# Keg_Cop_-_Devel.net
KiCad netlist of a schematic drawn in EAGLE
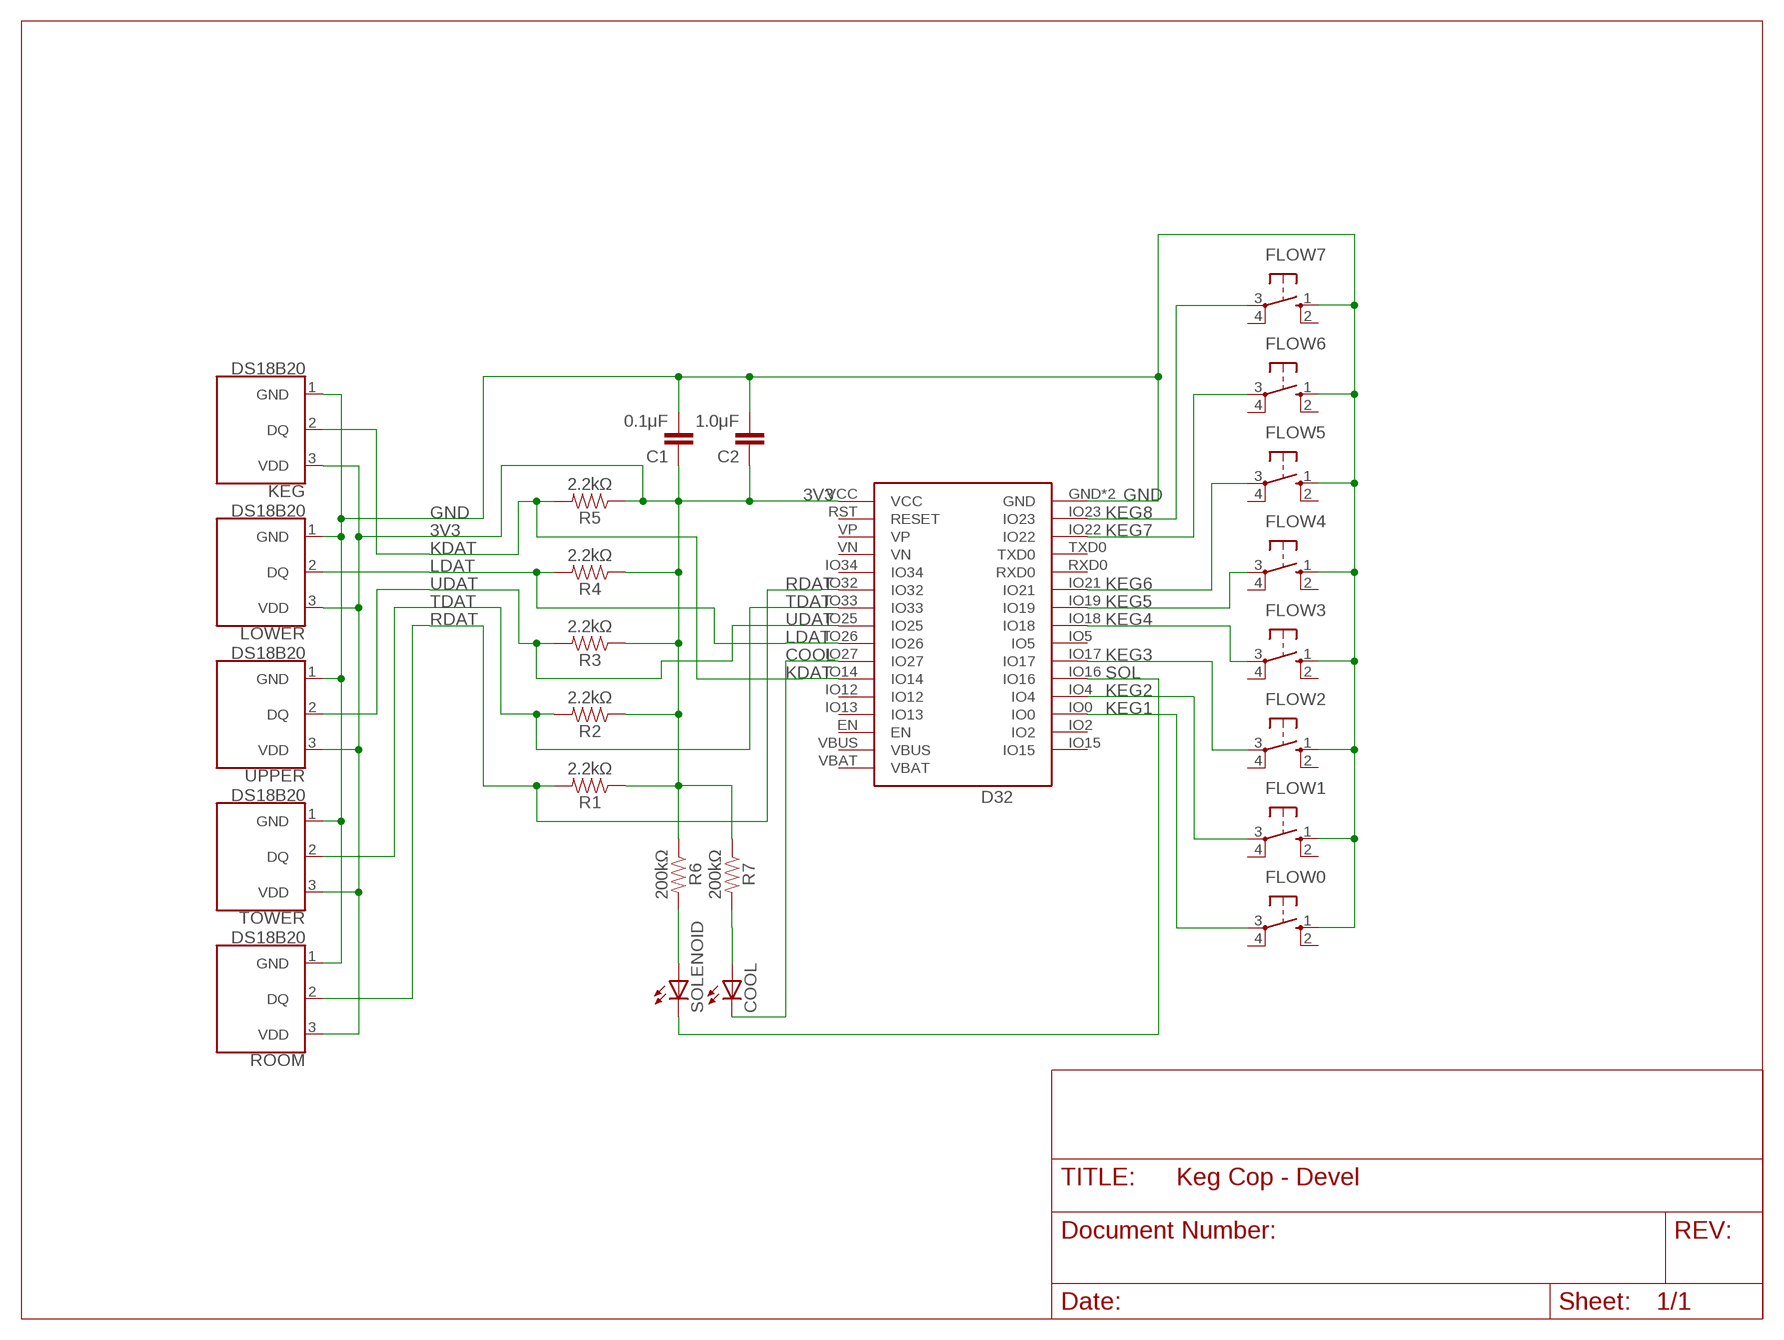
[diagram p0: schematic, sheet 1]

(export (version "E")
  (design (tool "Eeschema 10.0.6"))
  (components
    (comp (ref "C1")
      (value "0.1μF")
      (footprint "eagle-import:CAP_PTH-2.54")
      (libsource (lib "eagle-import") (part "CAP_CERAMIC_2.54"))
    )
    (comp (ref "C2")
      (value "1.0μF")
      (footprint "eagle-import:CAP_PTH-2.54")
      (libsource (lib "eagle-import") (part "CAP_CERAMIC_2.54"))
    )
    (comp (ref "COOL")
      (value "LED3MM")
      (footprint "eagle-import:LED3MM")
      (libsource (lib "eagle-import") (part "LED3MM"))
    )
    (comp (ref "D32")
      (value "Lolin D32")
      (footprint "eagle-import:D32_NO_BATT")
      (libsource (lib "eagle-import") (part "WEMOS-D32D32_NO_BATT"))
    )
    (comp (ref "FLOW0")
      (value "10-XX")
      (footprint "eagle-import:B3F-10XX")
      (fields (field (name "MPN") "B3F-1000"))
      (libsource (lib "eagle-import") (part "10-XX"))
    )
    (comp (ref "FLOW1")
      (value "10-XX")
      (footprint "eagle-import:B3F-10XX")
      (fields (field (name "MPN") "B3F-1000"))
      (libsource (lib "eagle-import") (part "10-XX"))
    )
    (comp (ref "FLOW2")
      (value "10-XX")
      (footprint "eagle-import:B3F-10XX")
      (fields (field (name "MPN") "B3F-1000"))
      (libsource (lib "eagle-import") (part "10-XX"))
    )
    (comp (ref "FLOW3")
      (value "10-XX")
      (footprint "eagle-import:B3F-10XX")
      (fields (field (name "MPN") "B3F-1000"))
      (libsource (lib "eagle-import") (part "10-XX"))
    )
    (comp (ref "FLOW4")
      (value "10-XX")
      (footprint "eagle-import:B3F-10XX")
      (fields (field (name "MPN") "B3F-1000"))
      (libsource (lib "eagle-import") (part "10-XX"))
    )
    (comp (ref "FLOW5")
      (value "10-XX")
      (footprint "eagle-import:B3F-10XX")
      (fields (field (name "MPN") "B3F-1000"))
      (libsource (lib "eagle-import") (part "10-XX"))
    )
    (comp (ref "FLOW6")
      (value "10-XX")
      (footprint "eagle-import:B3F-10XX")
      (fields (field (name "MPN") "B3F-1000"))
      (libsource (lib "eagle-import") (part "10-XX"))
    )
    (comp (ref "FLOW7")
      (value "10-XX")
      (footprint "eagle-import:B3F-10XX")
      (fields (field (name "MPN") "B3F-1000"))
      (libsource (lib "eagle-import") (part "10-XX"))
    )
    (comp (ref "KEG")
      (value "DS18B20")
      (footprint "eagle-import:TO-92-AMMO")
      (libsource (lib "eagle-import") (part "DS18B20"))
    )
    (comp (ref "LOWER")
      (value "DS18B20")
      (footprint "eagle-import:TO-92-AMMO")
      (libsource (lib "eagle-import") (part "DS18B20"))
    )
    (comp (ref "R1")
      (value "2.2kΩ")
      (footprint "eagle-import:AXIAL-0.3")
      (libsource (lib "eagle-import") (part "RESISTORAXIAL-0.3"))
    )
    (comp (ref "R2")
      (value "2.2kΩ")
      (footprint "eagle-import:AXIAL-0.3")
      (libsource (lib "eagle-import") (part "RESISTORAXIAL-0.3"))
    )
    (comp (ref "R3")
      (value "2.2kΩ")
      (footprint "eagle-import:AXIAL-0.3")
      (libsource (lib "eagle-import") (part "RESISTORAXIAL-0.3"))
    )
    (comp (ref "R4")
      (value "2.2kΩ")
      (footprint "eagle-import:AXIAL-0.3")
      (libsource (lib "eagle-import") (part "RESISTORAXIAL-0.3"))
    )
    (comp (ref "R5")
      (value "2.2kΩ")
      (footprint "eagle-import:AXIAL-0.3")
      (libsource (lib "eagle-import") (part "RESISTORAXIAL-0.3"))
    )
    (comp (ref "R6")
      (value "200kΩ")
      (footprint "eagle-import:AXIAL-0.3")
      (libsource (lib "eagle-import") (part "RESISTORAXIAL-0.3"))
    )
    (comp (ref "R7")
      (value "200kΩ")
      (footprint "eagle-import:AXIAL-0.3")
      (libsource (lib "eagle-import") (part "RESISTORAXIAL-0.3"))
    )
    (comp (ref "ROOM")
      (value "DS18B20")
      (footprint "eagle-import:TO-92-AMMO")
      (libsource (lib "eagle-import") (part "DS18B20"))
    )
    (comp (ref "SOLENOID")
      (value "LED3MM")
      (footprint "eagle-import:LED3MM")
      (libsource (lib "eagle-import") (part "LED3MM"))
    )
    (comp (ref "TOWER")
      (value "DS18B20")
      (footprint "eagle-import:TO-92-AMMO")
      (libsource (lib "eagle-import") (part "DS18B20"))
    )
    (comp (ref "UPPER")
      (value "DS18B20")
      (footprint "eagle-import:TO-92-AMMO")
      (libsource (lib "eagle-import") (part "DS18B20"))
    )
  )
  (nets
    (net (code "1") (name "/3V3") (class "Default")
      (node (ref "C1") (pin "1") (pinfunction "1_1") (pintype "passive"))
      (node (ref "C2") (pin "1") (pinfunction "1_1") (pintype "passive"))
      (node (ref "D32") (pin "VCC") (pinfunction "VCC_VCC") (pintype "power_in"))
      (node (ref "KEG") (pin "3") (pinfunction "VDD_3") (pintype "power_in"))
      (node (ref "LOWER") (pin "3") (pinfunction "VDD_3") (pintype "power_in"))
      (node (ref "R1") (pin "P$1") (pinfunction "1_P$1") (pintype "passive"))
      (node (ref "R2") (pin "P$1") (pinfunction "1_P$1") (pintype "passive"))
      (node (ref "R3") (pin "P$1") (pinfunction "1_P$1") (pintype "passive"))
      (node (ref "R4") (pin "P$1") (pinfunction "1_P$1") (pintype "passive"))
      (node (ref "R5") (pin "P$1") (pinfunction "1_P$1") (pintype "passive"))
      (node (ref "R6") (pin "P$1") (pinfunction "1_P$1") (pintype "passive"))
      (node (ref "R7") (pin "P$1") (pinfunction "1_P$1") (pintype "passive"))
      (node (ref "ROOM") (pin "3") (pinfunction "VDD_3") (pintype "power_in"))
      (node (ref "TOWER") (pin "3") (pinfunction "VDD_3") (pintype "power_in"))
      (node (ref "UPPER") (pin "3") (pinfunction "VDD_3") (pintype "power_in"))
    )
    (net (code "2") (name "/COOL") (class "Default")
      (node (ref "COOL") (pin "K") (pinfunction "C_K") (pintype "passive"))
      (node (ref "D32") (pin "IO27") (pinfunction "IO27_IO27") (pintype "bidirectional"))
    )
    (net (code "3") (name "/GND") (class "Default")
      (node (ref "C1") (pin "2") (pinfunction "2_2") (pintype "passive"))
      (node (ref "C2") (pin "2") (pinfunction "2_2") (pintype "passive"))
      (node (ref "D32") (pin "GND") (pinfunction "GND_GND") (pintype "power_in"))
      (node (ref "D32") (pin "GND2") (pinfunction "GND_GND2") (pintype "power_in"))
      (node (ref "FLOW0") (pin "1") (pinfunction "S_1") (pintype "passive"))
      (node (ref "FLOW1") (pin "1") (pinfunction "S_1") (pintype "passive"))
      (node (ref "FLOW2") (pin "1") (pinfunction "S_1") (pintype "passive"))
      (node (ref "FLOW3") (pin "1") (pinfunction "S_1") (pintype "passive"))
      (node (ref "FLOW4") (pin "1") (pinfunction "S_1") (pintype "passive"))
      (node (ref "FLOW5") (pin "1") (pinfunction "S_1") (pintype "passive"))
      (node (ref "FLOW6") (pin "1") (pinfunction "S_1") (pintype "passive"))
      (node (ref "FLOW7") (pin "1") (pinfunction "S_1") (pintype "passive"))
      (node (ref "KEG") (pin "1") (pinfunction "GND_1") (pintype "power_in"))
      (node (ref "LOWER") (pin "1") (pinfunction "GND_1") (pintype "power_in"))
      (node (ref "ROOM") (pin "1") (pinfunction "GND_1") (pintype "power_in"))
      (node (ref "TOWER") (pin "1") (pinfunction "GND_1") (pintype "power_in"))
      (node (ref "UPPER") (pin "1") (pinfunction "GND_1") (pintype "power_in"))
    )
    (net (code "4") (name "/KDAT") (class "Default")
      (node (ref "D32") (pin "IO14") (pinfunction "IO14_IO14") (pintype "bidirectional"))
      (node (ref "KEG") (pin "2") (pinfunction "DQ_2") (pintype "bidirectional"))
      (node (ref "R5") (pin "P$2") (pinfunction "2_P$2") (pintype "passive"))
    )
    (net (code "5") (name "/KEG1") (class "Default")
      (node (ref "D32") (pin "IO0") (pinfunction "IO0_IO0") (pintype "bidirectional"))
      (node (ref "FLOW0") (pin "3") (pinfunction "P_3") (pintype "passive"))
    )
    (net (code "6") (name "/KEG2") (class "Default")
      (node (ref "D32") (pin "IO4") (pinfunction "IO4_IO4") (pintype "bidirectional"))
      (node (ref "FLOW1") (pin "3") (pinfunction "P_3") (pintype "passive"))
    )
    (net (code "7") (name "/KEG3") (class "Default")
      (node (ref "D32") (pin "IO17") (pinfunction "IO17_IO17") (pintype "bidirectional"))
      (node (ref "FLOW2") (pin "3") (pinfunction "P_3") (pintype "passive"))
    )
    (net (code "8") (name "/KEG4") (class "Default")
      (node (ref "D32") (pin "IO18") (pinfunction "IO18_IO18") (pintype "bidirectional"))
      (node (ref "FLOW3") (pin "3") (pinfunction "P_3") (pintype "passive"))
    )
    (net (code "9") (name "/KEG5") (class "Default")
      (node (ref "D32") (pin "IO19") (pinfunction "IO19_IO19") (pintype "bidirectional"))
      (node (ref "FLOW4") (pin "3") (pinfunction "P_3") (pintype "passive"))
    )
    (net (code "10") (name "/KEG6") (class "Default")
      (node (ref "D32") (pin "IO21") (pinfunction "IO21_IO21") (pintype "bidirectional"))
      (node (ref "FLOW5") (pin "3") (pinfunction "P_3") (pintype "passive"))
    )
    (net (code "11") (name "/KEG7") (class "Default")
      (node (ref "D32") (pin "IO22") (pinfunction "IO22_IO22") (pintype "bidirectional"))
      (node (ref "FLOW6") (pin "3") (pinfunction "P_3") (pintype "passive"))
    )
    (net (code "12") (name "/KEG8") (class "Default")
      (node (ref "D32") (pin "IO23") (pinfunction "IO23_IO23") (pintype "bidirectional"))
      (node (ref "FLOW7") (pin "3") (pinfunction "P_3") (pintype "passive"))
    )
    (net (code "13") (name "/LDAT") (class "Default")
      (node (ref "D32") (pin "IO26") (pinfunction "IO26_IO26") (pintype "bidirectional"))
      (node (ref "LOWER") (pin "2") (pinfunction "DQ_2") (pintype "bidirectional"))
      (node (ref "R4") (pin "P$2") (pinfunction "2_P$2") (pintype "passive"))
    )
    (net (code "14") (name "/RDAT") (class "Default")
      (node (ref "D32") (pin "IO32") (pinfunction "IO32_IO32") (pintype "bidirectional"))
      (node (ref "R1") (pin "P$2") (pinfunction "2_P$2") (pintype "passive"))
      (node (ref "ROOM") (pin "2") (pinfunction "DQ_2") (pintype "bidirectional"))
    )
    (net (code "15") (name "/SOL") (class "Default")
      (node (ref "D32") (pin "IO16") (pinfunction "IO16_IO16") (pintype "bidirectional"))
      (node (ref "SOLENOID") (pin "K") (pinfunction "C_K") (pintype "passive"))
    )
    (net (code "16") (name "/TDAT") (class "Default")
      (node (ref "D32") (pin "IO33") (pinfunction "IO33_IO33") (pintype "bidirectional"))
      (node (ref "R2") (pin "P$2") (pinfunction "2_P$2") (pintype "passive"))
      (node (ref "TOWER") (pin "2") (pinfunction "DQ_2") (pintype "bidirectional"))
    )
    (net (code "17") (name "/UDAT") (class "Default")
      (node (ref "D32") (pin "IO25") (pinfunction "IO25_IO25") (pintype "bidirectional"))
      (node (ref "R3") (pin "P$2") (pinfunction "2_P$2") (pintype "passive"))
      (node (ref "UPPER") (pin "2") (pinfunction "DQ_2") (pintype "bidirectional"))
    )
    (net (code "18") (name "Net-(R6-2)") (class "Default")
      (node (ref "R6") (pin "P$2") (pinfunction "2_P$2") (pintype "passive"))
      (node (ref "SOLENOID") (pin "A") (pinfunction "A_A") (pintype "passive"))
    )
    (net (code "19") (name "Net-(R7-2)") (class "Default")
      (node (ref "COOL") (pin "A") (pinfunction "A_A") (pintype "passive"))
      (node (ref "R7") (pin "P$2") (pinfunction "2_P$2") (pintype "passive"))
    )
    (net (code "20") (name "unconnected-(D32-PadEN)") (class "Default")
      (node (ref "D32") (pin "EN") (pinfunction "EN_EN") (pintype "bidirectional"))
    )
    (net (code "21") (name "unconnected-(D32-PadIO2)") (class "Default")
      (node (ref "D32") (pin "IO2") (pinfunction "IO2_IO2") (pintype "bidirectional"))
    )
    (net (code "22") (name "unconnected-(D32-PadIO5)") (class "Default")
      (node (ref "D32") (pin "IO5") (pinfunction "IO5_IO5") (pintype "bidirectional"))
    )
    (net (code "23") (name "unconnected-(D32-PadIO12)") (class "Default")
      (node (ref "D32") (pin "IO12") (pinfunction "IO12_IO12") (pintype "bidirectional"))
    )
    (net (code "24") (name "unconnected-(D32-PadIO13)") (class "Default")
      (node (ref "D32") (pin "IO13") (pinfunction "IO13_IO13") (pintype "bidirectional"))
    )
    (net (code "25") (name "unconnected-(D32-PadIO15)") (class "Default")
      (node (ref "D32") (pin "IO15") (pinfunction "IO15_IO15") (pintype "bidirectional"))
    )
    (net (code "26") (name "unconnected-(D32-PadIO34)") (class "Default")
      (node (ref "D32") (pin "IO34") (pinfunction "IO34_IO34") (pintype "bidirectional"))
    )
    (net (code "27") (name "unconnected-(D32-PadRXD0)") (class "Default")
      (node (ref "D32") (pin "RXD0") (pinfunction "RXD0_RXD0") (pintype "input"))
    )
    (net (code "28") (name "unconnected-(D32-PadTXD0)") (class "Default")
      (node (ref "D32") (pin "TXD0") (pinfunction "TXD0_TXD0") (pintype "output"))
    )
    (net (code "29") (name "unconnected-(D32-PadVBAT)") (class "Default")
      (node (ref "D32") (pin "VBAT") (pinfunction "VBAT_VBAT") (pintype "bidirectional"))
    )
    (net (code "30") (name "unconnected-(D32-PadVBUS)") (class "Default")
      (node (ref "D32") (pin "VBUS") (pinfunction "VBUS_VBUS") (pintype "bidirectional"))
    )
    (net (code "31") (name "unconnected-(D32-PadVN)") (class "Default")
      (node (ref "D32") (pin "VN") (pinfunction "VN_VN") (pintype "bidirectional"))
    )
    (net (code "32") (name "unconnected-(D32-PadVP)") (class "Default")
      (node (ref "D32") (pin "VP") (pinfunction "VP_VP") (pintype "bidirectional"))
    )
    (net (code "33") (name "unconnected-(D32-RESET-PadRST)") (class "Default")
      (node (ref "D32") (pin "RST") (pinfunction "RESET_RST") (pintype "bidirectional"))
    )
    (net (code "34") (name "unconnected-(FLOW0-P1-Pad4)") (class "Default")
      (node (ref "FLOW0") (pin "4") (pinfunction "P1_4") (pintype "passive"))
    )
    (net (code "35") (name "unconnected-(FLOW0-S1-Pad2)") (class "Default")
      (node (ref "FLOW0") (pin "2") (pinfunction "S1_2") (pintype "passive"))
    )
    (net (code "36") (name "unconnected-(FLOW1-P1-Pad4)") (class "Default")
      (node (ref "FLOW1") (pin "4") (pinfunction "P1_4") (pintype "passive"))
    )
    (net (code "37") (name "unconnected-(FLOW1-S1-Pad2)") (class "Default")
      (node (ref "FLOW1") (pin "2") (pinfunction "S1_2") (pintype "passive"))
    )
    (net (code "38") (name "unconnected-(FLOW2-P1-Pad4)") (class "Default")
      (node (ref "FLOW2") (pin "4") (pinfunction "P1_4") (pintype "passive"))
    )
    (net (code "39") (name "unconnected-(FLOW2-S1-Pad2)") (class "Default")
      (node (ref "FLOW2") (pin "2") (pinfunction "S1_2") (pintype "passive"))
    )
    (net (code "40") (name "unconnected-(FLOW3-P1-Pad4)") (class "Default")
      (node (ref "FLOW3") (pin "4") (pinfunction "P1_4") (pintype "passive"))
    )
    (net (code "41") (name "unconnected-(FLOW3-S1-Pad2)") (class "Default")
      (node (ref "FLOW3") (pin "2") (pinfunction "S1_2") (pintype "passive"))
    )
    (net (code "42") (name "unconnected-(FLOW4-P1-Pad4)") (class "Default")
      (node (ref "FLOW4") (pin "4") (pinfunction "P1_4") (pintype "passive"))
    )
    (net (code "43") (name "unconnected-(FLOW4-S1-Pad2)") (class "Default")
      (node (ref "FLOW4") (pin "2") (pinfunction "S1_2") (pintype "passive"))
    )
    (net (code "44") (name "unconnected-(FLOW5-P1-Pad4)") (class "Default")
      (node (ref "FLOW5") (pin "4") (pinfunction "P1_4") (pintype "passive"))
    )
    (net (code "45") (name "unconnected-(FLOW5-S1-Pad2)") (class "Default")
      (node (ref "FLOW5") (pin "2") (pinfunction "S1_2") (pintype "passive"))
    )
    (net (code "46") (name "unconnected-(FLOW6-P1-Pad4)") (class "Default")
      (node (ref "FLOW6") (pin "4") (pinfunction "P1_4") (pintype "passive"))
    )
    (net (code "47") (name "unconnected-(FLOW6-S1-Pad2)") (class "Default")
      (node (ref "FLOW6") (pin "2") (pinfunction "S1_2") (pintype "passive"))
    )
    (net (code "48") (name "unconnected-(FLOW7-P1-Pad4)") (class "Default")
      (node (ref "FLOW7") (pin "4") (pinfunction "P1_4") (pintype "passive"))
    )
    (net (code "49") (name "unconnected-(FLOW7-S1-Pad2)") (class "Default")
      (node (ref "FLOW7") (pin "2") (pinfunction "S1_2") (pintype "passive"))
    )
  )
)
